# Thermal_Sens.net
KiCad netlist of a schematic drawn in Altium Designer
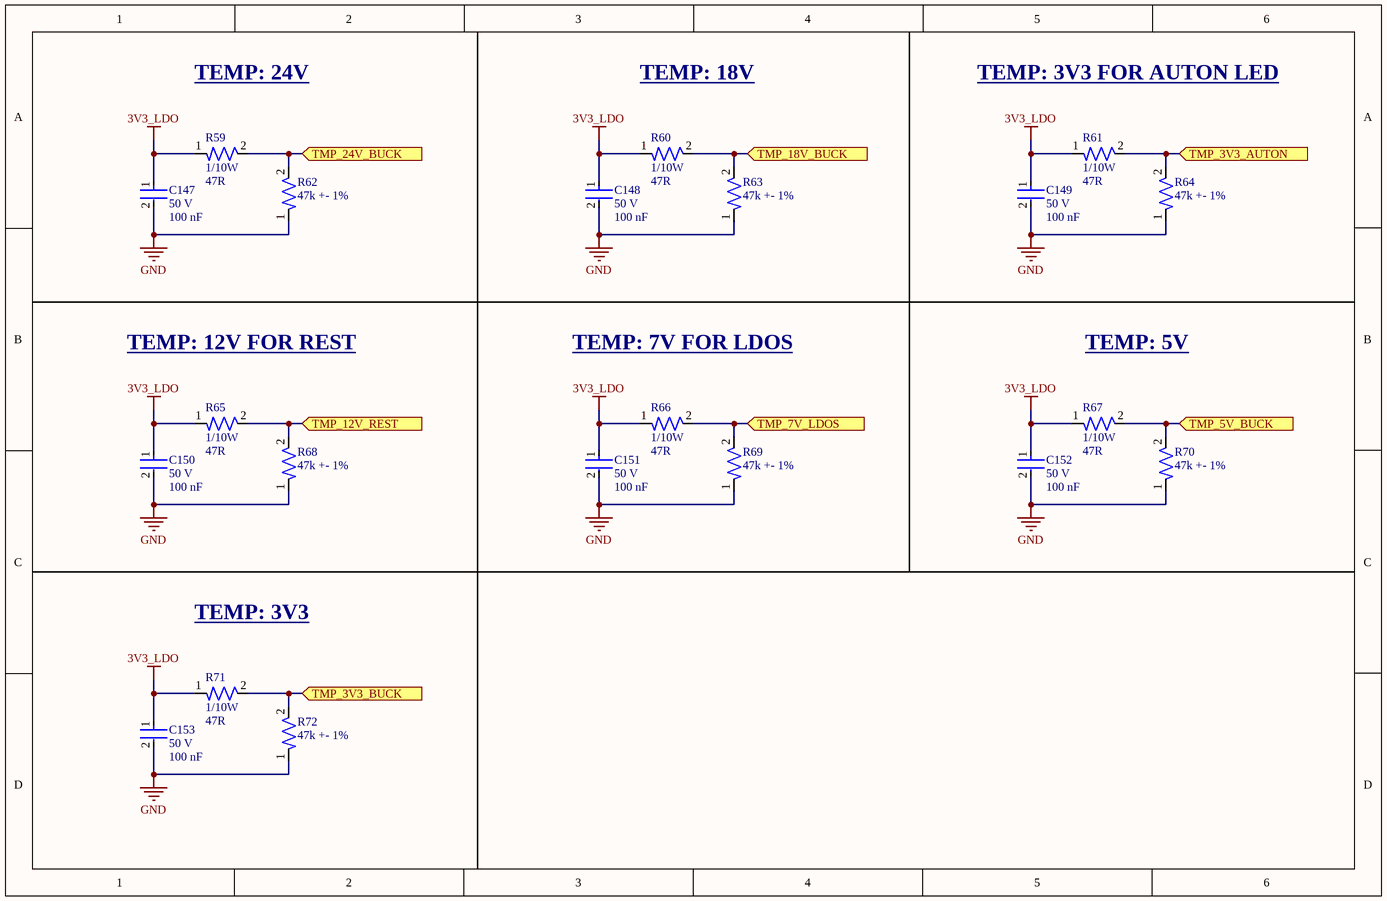
[diagram p0: Thermal_Sens.SchDoc]

(export (version "E")
  (design (tool "Eeschema 10.0.6"))
  (components
    (comp (ref "C147")
      (value "CC0805KRX7R9BB104")
      (footprint "CAP-0805")
      (description "CAP CER 0.1UF 50V X7R 0805")
      (fields (field (name "VOLTAGE RATING") "50 V") (field (name "CAPACITANCE") "100 nF"))
      (libsource (lib "JLC_25") (part "CAP-0.1U-0002"))
    )
    (comp (ref "C148")
      (value "CC0805KRX7R9BB104")
      (footprint "CAP-0805")
      (description "CAP CER 0.1UF 50V X7R 0805")
      (fields (field (name "VOLTAGE RATING") "50 V") (field (name "CAPACITANCE") "100 nF"))
      (libsource (lib "JLC_25") (part "CAP-0.1U-0002"))
    )
    (comp (ref "C149")
      (value "CC0805KRX7R9BB104")
      (footprint "CAP-0805")
      (description "CAP CER 0.1UF 50V X7R 0805")
      (fields (field (name "VOLTAGE RATING") "50 V") (field (name "CAPACITANCE") "100 nF"))
      (libsource (lib "JLC_25") (part "CAP-0.1U-0002"))
    )
    (comp (ref "C150")
      (value "CC0805KRX7R9BB104")
      (footprint "CAP-0805")
      (description "CAP CER 0.1UF 50V X7R 0805")
      (fields (field (name "VOLTAGE RATING") "50 V") (field (name "CAPACITANCE") "100 nF"))
      (libsource (lib "JLC_25") (part "CAP-0.1U-0002"))
    )
    (comp (ref "C151")
      (value "CC0805KRX7R9BB104")
      (footprint "CAP-0805")
      (description "CAP CER 0.1UF 50V X7R 0805")
      (fields (field (name "VOLTAGE RATING") "50 V") (field (name "CAPACITANCE") "100 nF"))
      (libsource (lib "JLC_25") (part "CAP-0.1U-0002"))
    )
    (comp (ref "C152")
      (value "CC0805KRX7R9BB104")
      (footprint "CAP-0805")
      (description "CAP CER 0.1UF 50V X7R 0805")
      (fields (field (name "VOLTAGE RATING") "50 V") (field (name "CAPACITANCE") "100 nF"))
      (libsource (lib "JLC_25") (part "CAP-0.1U-0002"))
    )
    (comp (ref "C153")
      (value "CC0805KRX7R9BB104")
      (footprint "CAP-0805")
      (description "CAP CER 0.1UF 50V X7R 0805")
      (fields (field (name "VOLTAGE RATING") "50 V") (field (name "CAPACITANCE") "100 nF"))
      (libsource (lib "JLC_25") (part "CAP-0.1U-0002"))
    )
    (comp (ref "R59")
      (value "RC0603FR-0747RL")
      (footprint "RES-0603")
      (description "RES 47 OHM 1% 1/10W 0603")
      (fields
        (field (name "TOLERANCE") "1%")
        (field (name "POWER") "1/10W")
        (field (name "RESISTANCE") "47R")
      )
      (libsource (lib "JLC_25") (part "RES-47-0001"))
    )
    (comp (ref "R60")
      (value "RC0603FR-0747RL")
      (footprint "RES-0603")
      (description "RES 47 OHM 1% 1/10W 0603")
      (fields
        (field (name "TOLERANCE") "1%")
        (field (name "POWER") "1/10W")
        (field (name "RESISTANCE") "47R")
      )
      (libsource (lib "JLC_25") (part "RES-47-0001"))
    )
    (comp (ref "R61")
      (value "RC0603FR-0747RL")
      (footprint "RES-0603")
      (description "RES 47 OHM 1% 1/10W 0603")
      (fields
        (field (name "TOLERANCE") "1%")
        (field (name "POWER") "1/10W")
        (field (name "RESISTANCE") "47R")
      )
      (libsource (lib "JLC_25") (part "RES-47-0001"))
    )
    (comp (ref "R62")
      (value "TMP6431DECR")
      (footprint "RES-0402")
      (description "PTC Thermistor 47 kOhms 0402 (1006 Metric)")
      (fields (field (name "RESISTANCE") "47k +- 1%"))
      (libsource (lib "JLC_25") (part "RES-47k-0001"))
    )
    (comp (ref "R63")
      (value "TMP6431DECR")
      (footprint "RES-0402")
      (description "PTC Thermistor 47 kOhms 0402 (1006 Metric)")
      (fields (field (name "RESISTANCE") "47k +- 1%"))
      (libsource (lib "JLC_25") (part "RES-47k-0001"))
    )
    (comp (ref "R64")
      (value "TMP6431DECR")
      (footprint "RES-0402")
      (description "PTC Thermistor 47 kOhms 0402 (1006 Metric)")
      (fields (field (name "RESISTANCE") "47k +- 1%"))
      (libsource (lib "JLC_25") (part "RES-47k-0001"))
    )
    (comp (ref "R65")
      (value "RC0603FR-0747RL")
      (footprint "RES-0603")
      (description "RES 47 OHM 1% 1/10W 0603")
      (fields
        (field (name "TOLERANCE") "1%")
        (field (name "POWER") "1/10W")
        (field (name "RESISTANCE") "47R")
      )
      (libsource (lib "JLC_25") (part "RES-47-0001"))
    )
    (comp (ref "R66")
      (value "RC0603FR-0747RL")
      (footprint "RES-0603")
      (description "RES 47 OHM 1% 1/10W 0603")
      (fields
        (field (name "TOLERANCE") "1%")
        (field (name "POWER") "1/10W")
        (field (name "RESISTANCE") "47R")
      )
      (libsource (lib "JLC_25") (part "RES-47-0001"))
    )
    (comp (ref "R67")
      (value "RC0603FR-0747RL")
      (footprint "RES-0603")
      (description "RES 47 OHM 1% 1/10W 0603")
      (fields
        (field (name "TOLERANCE") "1%")
        (field (name "POWER") "1/10W")
        (field (name "RESISTANCE") "47R")
      )
      (libsource (lib "JLC_25") (part "RES-47-0001"))
    )
    (comp (ref "R68")
      (value "TMP6431DECR")
      (footprint "RES-0402")
      (description "PTC Thermistor 47 kOhms 0402 (1006 Metric)")
      (fields (field (name "RESISTANCE") "47k +- 1%"))
      (libsource (lib "JLC_25") (part "RES-47k-0001"))
    )
    (comp (ref "R69")
      (value "TMP6431DECR")
      (footprint "RES-0402")
      (description "PTC Thermistor 47 kOhms 0402 (1006 Metric)")
      (fields (field (name "RESISTANCE") "47k +- 1%"))
      (libsource (lib "JLC_25") (part "RES-47k-0001"))
    )
    (comp (ref "R70")
      (value "TMP6431DECR")
      (footprint "RES-0402")
      (description "PTC Thermistor 47 kOhms 0402 (1006 Metric)")
      (fields (field (name "RESISTANCE") "47k +- 1%"))
      (libsource (lib "JLC_25") (part "RES-47k-0001"))
    )
    (comp (ref "R71")
      (value "RC0603FR-0747RL")
      (footprint "RES-0603")
      (description "RES 47 OHM 1% 1/10W 0603")
      (fields
        (field (name "TOLERANCE") "1%")
        (field (name "POWER") "1/10W")
        (field (name "RESISTANCE") "47R")
      )
      (libsource (lib "JLC_25") (part "RES-47-0001"))
    )
    (comp (ref "R72")
      (value "TMP6431DECR")
      (footprint "RES-0402")
      (description "PTC Thermistor 47 kOhms 0402 (1006 Metric)")
      (fields (field (name "RESISTANCE") "47k +- 1%"))
      (libsource (lib "JLC_25") (part "RES-47k-0001"))
    )
  )
  (nets
    (net (code "1") (name "/TMP_3V3_AUTON") (class "Default")
      (node (ref "R61") (pin "2") (pinfunction "2_2") (pintype "passive"))
      (node (ref "R64") (pin "2") (pinfunction "2_2") (pintype "passive"))
    )
    (net (code "2") (name "/TMP_3V3_BUCK") (class "Default")
      (node (ref "R71") (pin "2") (pinfunction "2_2") (pintype "passive"))
      (node (ref "R72") (pin "2") (pinfunction "2_2") (pintype "passive"))
    )
    (net (code "3") (name "/TMP_5V_BUCK") (class "Default")
      (node (ref "R67") (pin "2") (pinfunction "2_2") (pintype "passive"))
      (node (ref "R70") (pin "2") (pinfunction "2_2") (pintype "passive"))
    )
    (net (code "4") (name "/TMP_7V_LDOS") (class "Default")
      (node (ref "R66") (pin "2") (pinfunction "2_2") (pintype "passive"))
      (node (ref "R69") (pin "2") (pinfunction "2_2") (pintype "passive"))
    )
    (net (code "5") (name "/TMP_12V_REST") (class "Default")
      (node (ref "R65") (pin "2") (pinfunction "2_2") (pintype "passive"))
      (node (ref "R68") (pin "2") (pinfunction "2_2") (pintype "passive"))
    )
    (net (code "6") (name "/TMP_18V_BUCK") (class "Default")
      (node (ref "R60") (pin "2") (pinfunction "2_2") (pintype "passive"))
      (node (ref "R63") (pin "2") (pinfunction "2_2") (pintype "passive"))
    )
    (net (code "7") (name "/TMP_24V_BUCK") (class "Default")
      (node (ref "R59") (pin "2") (pinfunction "2_2") (pintype "passive"))
      (node (ref "R62") (pin "2") (pinfunction "2_2") (pintype "passive"))
    )
    (net (code "8") (name "3V3_LDO") (class "Default")
      (node (ref "C147") (pin "1") (pinfunction "1_1") (pintype "passive"))
      (node (ref "C148") (pin "1") (pinfunction "1_1") (pintype "passive"))
      (node (ref "C149") (pin "1") (pinfunction "1_1") (pintype "passive"))
      (node (ref "C150") (pin "1") (pinfunction "1_1") (pintype "passive"))
      (node (ref "C151") (pin "1") (pinfunction "1_1") (pintype "passive"))
      (node (ref "C152") (pin "1") (pinfunction "1_1") (pintype "passive"))
      (node (ref "C153") (pin "1") (pinfunction "1_1") (pintype "passive"))
      (node (ref "R59") (pin "1") (pinfunction "1_1") (pintype "passive"))
      (node (ref "R60") (pin "1") (pinfunction "1_1") (pintype "passive"))
      (node (ref "R61") (pin "1") (pinfunction "1_1") (pintype "passive"))
      (node (ref "R65") (pin "1") (pinfunction "1_1") (pintype "passive"))
      (node (ref "R66") (pin "1") (pinfunction "1_1") (pintype "passive"))
      (node (ref "R67") (pin "1") (pinfunction "1_1") (pintype "passive"))
      (node (ref "R71") (pin "1") (pinfunction "1_1") (pintype "passive"))
    )
    (net (code "9") (name "GND") (class "Default")
      (node (ref "C147") (pin "2") (pinfunction "2_2") (pintype "passive"))
      (node (ref "C148") (pin "2") (pinfunction "2_2") (pintype "passive"))
      (node (ref "C149") (pin "2") (pinfunction "2_2") (pintype "passive"))
      (node (ref "C150") (pin "2") (pinfunction "2_2") (pintype "passive"))
      (node (ref "C151") (pin "2") (pinfunction "2_2") (pintype "passive"))
      (node (ref "C152") (pin "2") (pinfunction "2_2") (pintype "passive"))
      (node (ref "C153") (pin "2") (pinfunction "2_2") (pintype "passive"))
      (node (ref "R62") (pin "1") (pinfunction "1_1") (pintype "passive"))
      (node (ref "R63") (pin "1") (pinfunction "1_1") (pintype "passive"))
      (node (ref "R64") (pin "1") (pinfunction "1_1") (pintype "passive"))
      (node (ref "R68") (pin "1") (pinfunction "1_1") (pintype "passive"))
      (node (ref "R69") (pin "1") (pinfunction "1_1") (pintype "passive"))
      (node (ref "R70") (pin "1") (pinfunction "1_1") (pintype "passive"))
      (node (ref "R72") (pin "1") (pinfunction "1_1") (pintype "passive"))
    )
  )
)
